# Qwiic_Adaptive_Switch_Output.net
KiCad netlist of a schematic drawn in EAGLE
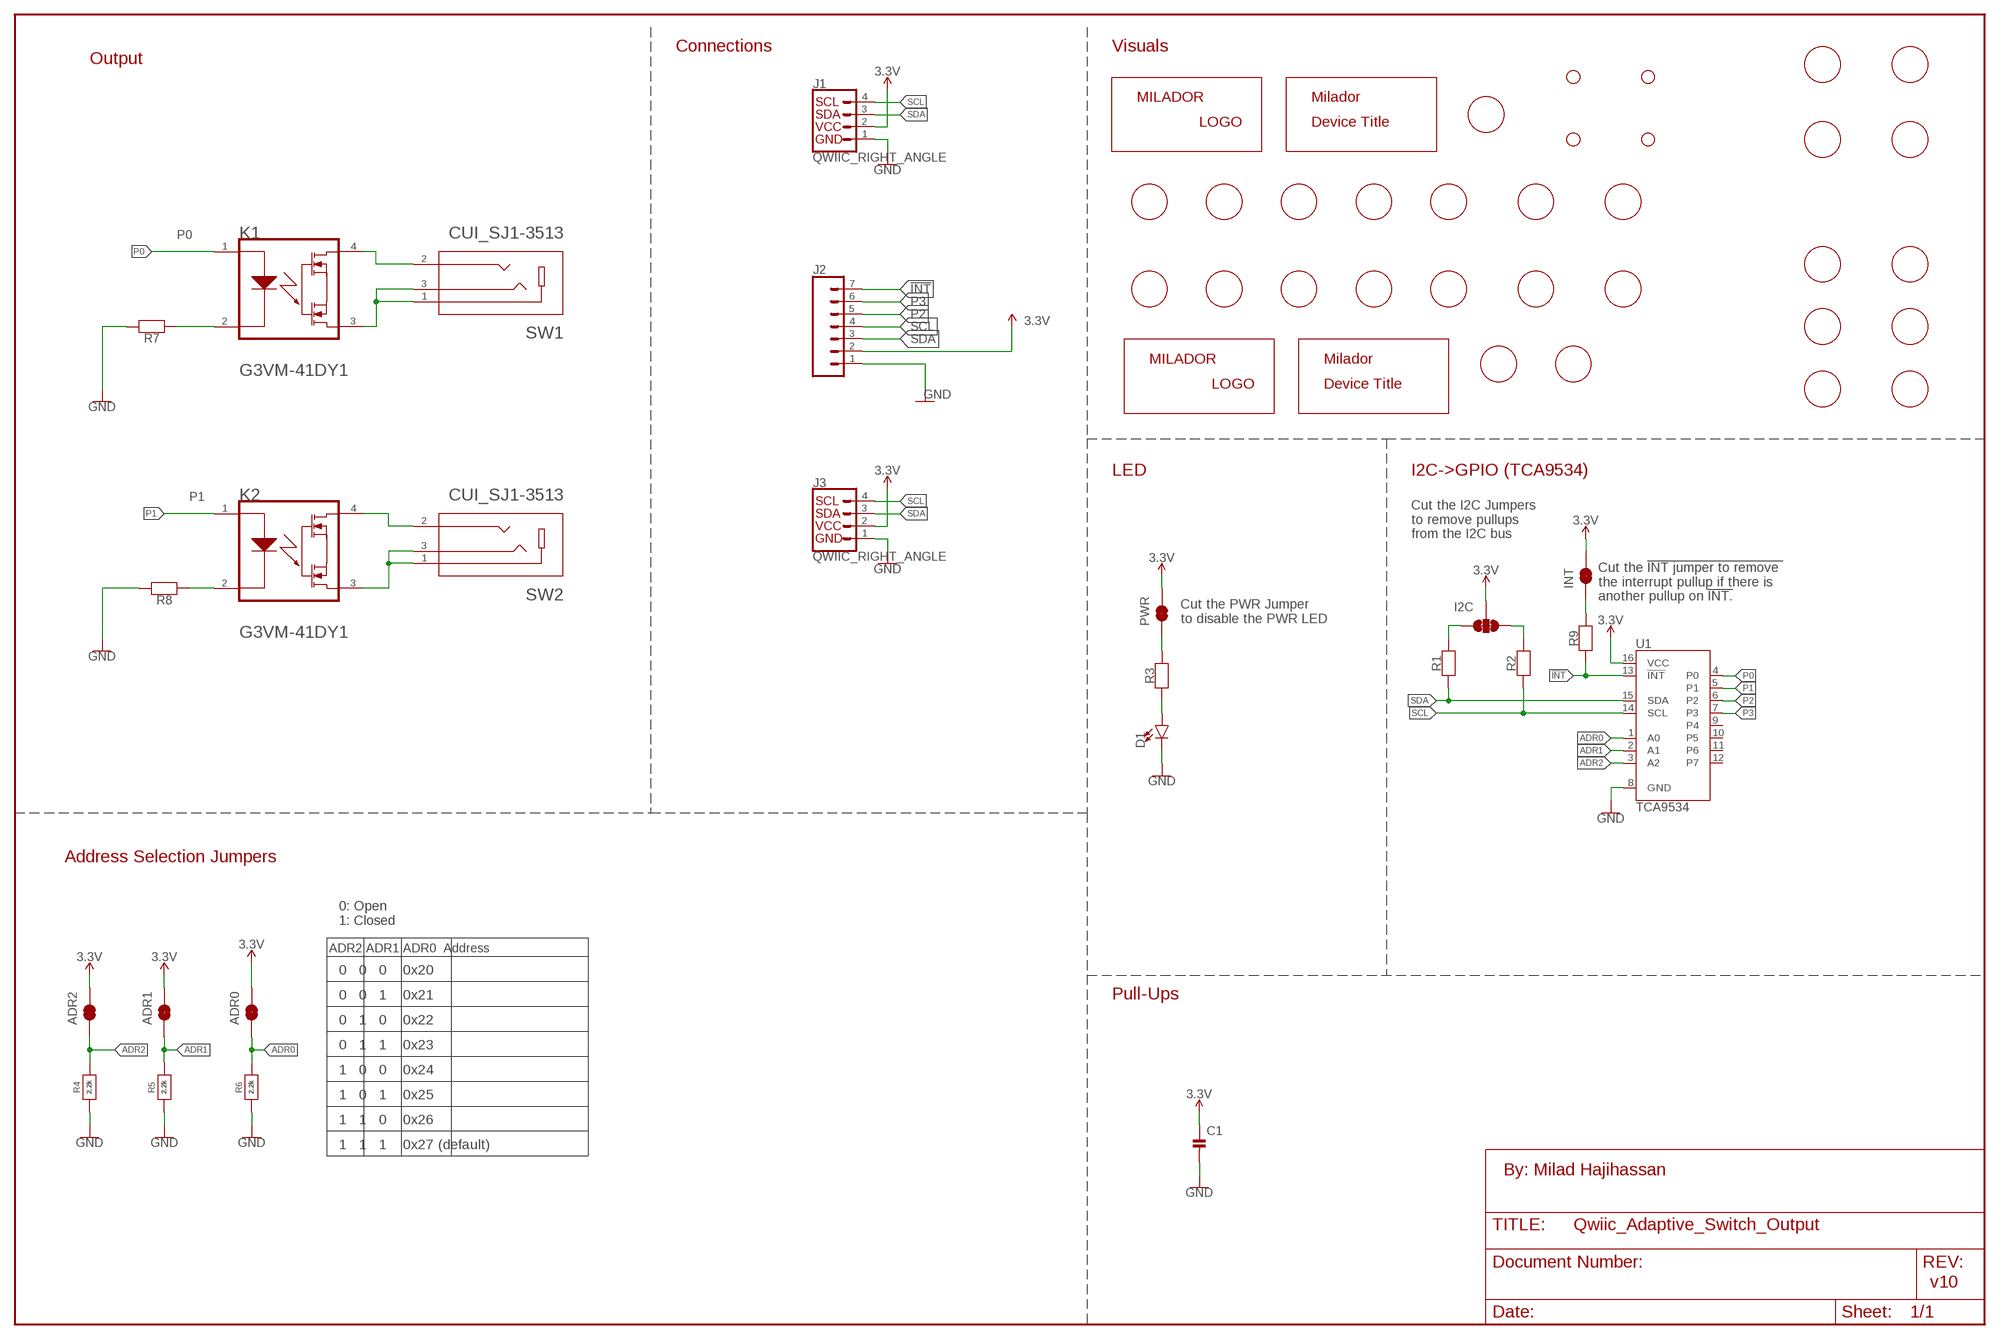
[diagram p0: schematic, sheet 1]

(export (version "E")
  (design (tool "Eeschema 10.0.6"))
  (components
    (comp (ref "ADR0")
      (value "JUMPERS-SMT_2_NC_TRACE_SILK")
      (footprint "eagle-import:JUMPERS_SMT-JUMPER_2_NC_TRACE_SILK")
      (libsource (lib "eagle-import") (part "JUMPERS-SMT_2_NC_TRACE_SILK"))
    )
    (comp (ref "ADR1")
      (value "JUMPERS-SMT_2_NC_TRACE_SILK")
      (footprint "eagle-import:JUMPERS_SMT-JUMPER_2_NC_TRACE_SILK")
      (libsource (lib "eagle-import") (part "JUMPERS-SMT_2_NC_TRACE_SILK"))
    )
    (comp (ref "ADR2")
      (value "JUMPERS-SMT_2_NC_TRACE_SILK")
      (footprint "eagle-import:JUMPERS_SMT-JUMPER_2_NC_TRACE_SILK")
      (libsource (lib "eagle-import") (part "JUMPERS-SMT_2_NC_TRACE_SILK"))
    )
    (comp (ref "C1")
      (value "0.1uF")
      (footprint "eagle-import:0805-MP")
      (libsource (lib "eagle-import") (part "CAP_CERAMIC-0805-MP"))
    )
    (comp (ref "D1")
      (value "RED")
      (footprint "eagle-import:CHIPLED_0805_NOOUTLINE")
      (libsource (lib "eagle-import") (part "LED0805_NOOUTLINE"))
    )
    (comp (ref "H1")
      (value "STAND-OFF-3.3")
      (footprint "eagle-import:STAND-OFF-3.3")
      (libsource (lib "eagle-import") (part "STAND-OFF-3.3"))
    )
    (comp (ref "H2")
      (value "STAND-OFF-3.3")
      (footprint "eagle-import:STAND-OFF-3.3")
      (libsource (lib "eagle-import") (part "STAND-OFF-3.3"))
    )
    (comp (ref "H3")
      (value "STAND-OFF-3.3")
      (footprint "eagle-import:STAND-OFF-3.3")
      (libsource (lib "eagle-import") (part "STAND-OFF-3.3"))
    )
    (comp (ref "H4")
      (value "STAND-OFF-3.3")
      (footprint "eagle-import:STAND-OFF-3.3")
      (libsource (lib "eagle-import") (part "STAND-OFF-3.3"))
    )
    (comp (ref "I2C")
      (value "JUMPERS_JUMPER-SMT_3_2-NC_TRACE_SILK")
      (footprint "eagle-import:JUMPERS_SMT-JUMPER_3_2-NC_TRACE_SILK")
      (libsource (lib "eagle-import") (part "JUMPERS_JUMPER-SMT_3_2-NC_TRACE_SILK"))
    )
    (comp (ref "INT")
      (value "JUMPERS-SMT_2_NC_TRACE_SILK")
      (footprint "eagle-import:JUMPERS_SMT-JUMPER_2_NC_TRACE_SILK")
      (libsource (lib "eagle-import") (part "JUMPERS-SMT_2_NC_TRACE_SILK"))
    )
    (comp (ref "J1")
      (value "QWIIC_RIGHT_ANGLE")
      (footprint "eagle-import:CONNECTORS_JST04_1MM_RA")
      (fields (field (name "PROD_ID") "CONN-13694"))
      (libsource (lib "eagle-import") (part "QWIIC_CONNECTORSJS-1MM"))
    )
    (comp (ref "J2")
      (value "CONNECTORS_CONN_071X07_NO_SILK")
      (footprint "eagle-import:CONNECTORS_1X07_NO_SILK")
      (libsource (lib "eagle-import") (part "CONNECTORS_CONN_071X07_NO_SILK"))
    )
    (comp (ref "J3")
      (value "QWIIC_RIGHT_ANGLE")
      (footprint "eagle-import:CONNECTORS_JST04_1MM_RA")
      (fields (field (name "PROD_ID") "CONN-13694"))
      (libsource (lib "eagle-import") (part "QWIIC_CONNECTORSJS-1MM"))
    )
    (comp (ref "K1")
      (value "G3VM-41DY1")
      (footprint "eagle-import:G3VM-41DY1")
      (libsource (lib "eagle-import") (part "G3VM-41DY1"))
    )
    (comp (ref "K2")
      (value "G3VM-41DY1")
      (footprint "eagle-import:G3VM-41DY1")
      (libsource (lib "eagle-import") (part "G3VM-41DY1"))
    )
    (comp (ref "LABEL_!INT_BOTTOM")
      (value "MILADOR-LABEL-!INT")
      (footprint "eagle-import:LABEL-!INT")
      (libsource (lib "eagle-import") (part "MILADOR-LABEL-!INT"))
    )
    (comp (ref "LABEL_!INT_TOP")
      (value "MILADOR-LABEL-!INT")
      (footprint "eagle-import:LABEL-!INT")
      (libsource (lib "eagle-import") (part "MILADOR-LABEL-!INT"))
    )
    (comp (ref "LABEL_3V_BOTTOM")
      (value "MILADOR-LABEL-3V")
      (footprint "eagle-import:LABEL-3V")
      (libsource (lib "eagle-import") (part "MILADOR-LABEL-3V"))
    )
    (comp (ref "LABEL_3V_TOP")
      (value "MILADOR-LABEL-3V")
      (footprint "eagle-import:LABEL-3V")
      (libsource (lib "eagle-import") (part "MILADOR-LABEL-3V"))
    )
    (comp (ref "LABEL_ADR0")
      (value "MILADOR-LABEL-ADR0")
      (footprint "eagle-import:LABEL-ADR0")
      (libsource (lib "eagle-import") (part "MILADOR-LABEL-ADR0"))
    )
    (comp (ref "LABEL_ADR1")
      (value "MILADOR-LABEL-ADR1")
      (footprint "eagle-import:LABEL-ADR1")
      (libsource (lib "eagle-import") (part "MILADOR-LABEL-ADR1"))
    )
    (comp (ref "LABEL_ADR2")
      (value "MILADOR-LABEL-ADR2")
      (footprint "eagle-import:LABEL-ADR2")
      (libsource (lib "eagle-import") (part "MILADOR-LABEL-ADR2"))
    )
    (comp (ref "LABEL_GND_BOTTOM")
      (value "MILADOR-LABEL-GND")
      (footprint "eagle-import:LABEL-GND")
      (libsource (lib "eagle-import") (part "MILADOR-LABEL-GND"))
    )
    (comp (ref "LABEL_GND_TOP")
      (value "MILADOR-LABEL-GND")
      (footprint "eagle-import:LABEL-GND")
      (libsource (lib "eagle-import") (part "MILADOR-LABEL-GND"))
    )
    (comp (ref "LABEL_I2C")
      (value "MILADOR-LABEL-I2C")
      (footprint "eagle-import:LABEL-I2C")
      (libsource (lib "eagle-import") (part "MILADOR-LABEL-I2C"))
    )
    (comp (ref "LABEL_I2C_ADDRESS")
      (value "MILADOR-LABEL-ADDRESS-0X27")
      (footprint "eagle-import:LABEL-ADDRESS-27")
      (libsource (lib "eagle-import") (part "MILADOR-LABEL-ADDRESS-0X27"))
    )
    (comp (ref "LABEL_INT")
      (value "MILADOR-LABEL-INT")
      (footprint "eagle-import:LABEL-INT")
      (libsource (lib "eagle-import") (part "MILADOR-LABEL-INT"))
    )
    (comp (ref "LABEL_MILADOR_BOTTOM")
      (value "MILADOR-LOGO-")
      (footprint "eagle-import:MILADOR_LOGO1")
      (libsource (lib "eagle-import") (part "MILADOR-LOGO-"))
    )
    (comp (ref "LABEL_MILADOR_TOP")
      (value "MILADOR-LOGO-")
      (footprint "eagle-import:MILADOR_LOGO1")
      (libsource (lib "eagle-import") (part "MILADOR-LOGO-"))
    )
    (comp (ref "LABEL_OUTPUT_BOTTOM")
      (value "MILADOR-SWITCH-NAME-SW-OUTPUT")
      (footprint "eagle-import:SWITCH-OUTPUT")
      (libsource (lib "eagle-import") (part "MILADOR-SWITCH-NAME-SW-OUTPUT"))
    )
    (comp (ref "LABEL_OUTPUT_TOP")
      (value "MILADOR-SWITCH-NAME-SW-OUTPUT")
      (footprint "eagle-import:SWITCH-OUTPUT")
      (libsource (lib "eagle-import") (part "MILADOR-SWITCH-NAME-SW-OUTPUT"))
    )
    (comp (ref "LABEL_P0_BOTTOM")
      (value "MILADOR-LABEL-P0")
      (footprint "eagle-import:LABEL-P0")
      (libsource (lib "eagle-import") (part "MILADOR-LABEL-P0"))
    )
    (comp (ref "LABEL_P1_BOTTOM")
      (value "MILADOR-LABEL-P1")
      (footprint "eagle-import:LABEL-P1")
      (libsource (lib "eagle-import") (part "MILADOR-LABEL-P1"))
    )
    (comp (ref "LABEL_P2_BOTTOM")
      (value "MILADOR-LABEL-P2")
      (footprint "eagle-import:LABEL-P2")
      (libsource (lib "eagle-import") (part "MILADOR-LABEL-P2"))
    )
    (comp (ref "LABEL_P2_TOP")
      (value "MILADOR-LABEL-P2")
      (footprint "eagle-import:LABEL-P2")
      (libsource (lib "eagle-import") (part "MILADOR-LABEL-P2"))
    )
    (comp (ref "LABEL_P3_BOTTOM")
      (value "MILADOR-LABEL-P3")
      (footprint "eagle-import:LABEL-P3")
      (libsource (lib "eagle-import") (part "MILADOR-LABEL-P3"))
    )
    (comp (ref "LABEL_P3_TOP")
      (value "MILADOR-LABEL-P3")
      (footprint "eagle-import:LABEL-P3")
      (libsource (lib "eagle-import") (part "MILADOR-LABEL-P3"))
    )
    (comp (ref "LABEL_PWR")
      (value "MILADOR-LABEL-PWR")
      (footprint "eagle-import:LABEL-PWR")
      (libsource (lib "eagle-import") (part "MILADOR-LABEL-PWR"))
    )
    (comp (ref "LABEL_SW1")
      (value "MILADOR-SWITCH-NAME-SW1")
      (footprint "eagle-import:SWITCH-SW1")
      (libsource (lib "eagle-import") (part "MILADOR-SWITCH-NAME-SW1"))
    )
    (comp (ref "LABEL_SW2")
      (value "MILADOR-SWITCH-NAME-SW2")
      (footprint "eagle-import:SWITCH-SW2")
      (libsource (lib "eagle-import") (part "MILADOR-SWITCH-NAME-SW2"))
    )
    (comp (ref "LABEL_TITLE_BOTTOM")
      (value "MILADOR-DEVICE-QWIIC-SWITCH")
      (footprint "eagle-import:MILADOR_QWIIC_SWITCH")
      (libsource (lib "eagle-import") (part "MILADOR-DEVICE-QWIIC-SWITCH"))
    )
    (comp (ref "LABEL_TITLE_TOP")
      (value "MILADOR-DEVICE-QWIIC-SWITCH-SM")
      (footprint "eagle-import:MILADOR_QWIIC_SWITCH_SM")
      (libsource (lib "eagle-import") (part "MILADOR-DEVICE-QWIIC-SWITCH-SM"))
    )
    (comp (ref "LABE_SCL_BOTTOM")
      (value "MILADOR-LABEL-SCL")
      (footprint "eagle-import:LABEL-SCL")
      (libsource (lib "eagle-import") (part "MILADOR-LABEL-SCL"))
    )
    (comp (ref "LABE_SCL_TOP")
      (value "MILADOR-LABEL-SCL")
      (footprint "eagle-import:LABEL-SCL")
      (libsource (lib "eagle-import") (part "MILADOR-LABEL-SCL"))
    )
    (comp (ref "LABE_SDA_BOTTOM")
      (value "MILADOR-LABEL-SDA")
      (footprint "eagle-import:LABEL-SDA")
      (libsource (lib "eagle-import") (part "MILADOR-LABEL-SDA"))
    )
    (comp (ref "LABE_SDA_TOP")
      (value "MILADOR-LABEL-SDA")
      (footprint "eagle-import:LABEL-SDA")
      (libsource (lib "eagle-import") (part "MILADOR-LABEL-SDA"))
    )
    (comp (ref "PWR")
      (value "JUMPERS-SMT_2_NC_TRACE_SILK")
      (footprint "eagle-import:JUMPERS_SMT-JUMPER_2_NC_TRACE_SILK")
      (libsource (lib "eagle-import") (part "JUMPERS-SMT_2_NC_TRACE_SILK"))
    )
    (comp (ref "R1")
      (value "2.2k")
      (footprint "eagle-import:0805-MP")
      (libsource (lib "eagle-import") (part "RESISTOR-0805-MP"))
    )
    (comp (ref "R2")
      (value "2.2k")
      (footprint "eagle-import:0805-MP")
      (libsource (lib "eagle-import") (part "RESISTOR-0805-MP"))
    )
    (comp (ref "R3")
      (value "1k")
      (footprint "eagle-import:0805-MP")
      (libsource (lib "eagle-import") (part "RESISTOR-0805-MP"))
    )
    (comp (ref "R4")
      (value "2.2k")
      (footprint "eagle-import:0805-MP")
      (libsource (lib "eagle-import") (part "RESISTOR-0805-MP"))
    )
    (comp (ref "R5")
      (value "2.2k")
      (footprint "eagle-import:0805-MP")
      (libsource (lib "eagle-import") (part "RESISTOR-0805-MP"))
    )
    (comp (ref "R6")
      (value "2.2k")
      (footprint "eagle-import:0805-MP")
      (libsource (lib "eagle-import") (part "RESISTOR-0805-MP"))
    )
    (comp (ref "R7")
      (value "220")
      (footprint "eagle-import:0805-MP")
      (libsource (lib "eagle-import") (part "RESISTOR-0805-MP"))
    )
    (comp (ref "R8")
      (value "220")
      (footprint "eagle-import:0805-MP")
      (libsource (lib "eagle-import") (part "RESISTOR-0805-MP"))
    )
    (comp (ref "R9")
      (value "10k")
      (footprint "eagle-import:0805-MP")
      (libsource (lib "eagle-import") (part "RESISTOR-0805-MP"))
    )
    (comp (ref "SW1")
      (value "CUI_SJ1-3513")
      (footprint "eagle-import:CUI_SJ1-3513")
      (libsource (lib "eagle-import") (part "CUI_SJ1-3513"))
    )
    (comp (ref "SW2")
      (value "CUI_SJ1-3513")
      (footprint "eagle-import:CUI_SJ1-3513")
      (libsource (lib "eagle-import") (part "CUI_SJ1-3513"))
    )
    (comp (ref "U1")
      (value "TCA9534")
      (footprint "eagle-import:16SOIC")
      (libsource (lib "eagle-import") (part "TCA9534DWR"))
    )
  )
  (nets
    (net (code "1") (name "/~{INT}") (class "Default")
      (node (ref "J2") (pin "7") (pinfunction "7_7") (pintype "passive"))
      (node (ref "R9") (pin "1") (pinfunction "1_1") (pintype "passive"))
      (node (ref "U1") (pin "13") (pinfunction "~{INT}_13") (pintype "bidirectional"))
    )
    (net (code "2") (name "3.3V") (class "Default")
      (node (ref "ADR0") (pin "2") (pinfunction "2_2") (pintype "passive"))
      (node (ref "ADR1") (pin "2") (pinfunction "2_2") (pintype "passive"))
      (node (ref "ADR2") (pin "2") (pinfunction "2_2") (pintype "passive"))
      (node (ref "C1") (pin "1") (pinfunction "1_1") (pintype "passive"))
      (node (ref "I2C") (pin "2") (pinfunction "2_2") (pintype "passive"))
      (node (ref "INT") (pin "2") (pinfunction "2_2") (pintype "passive"))
      (node (ref "J1") (pin "2") (pinfunction "2_2") (pintype "power_in"))
      (node (ref "J2") (pin "2") (pinfunction "2_2") (pintype "passive"))
      (node (ref "J3") (pin "2") (pinfunction "2_2") (pintype "power_in"))
      (node (ref "PWR") (pin "2") (pinfunction "2_2") (pintype "passive"))
      (node (ref "U1") (pin "16") (pinfunction "VCC_16") (pintype "bidirectional"))
    )
    (net (code "3") (name "ADR0") (class "Default")
      (node (ref "ADR0") (pin "1") (pinfunction "1_1") (pintype "passive"))
      (node (ref "R6") (pin "2") (pinfunction "2_2") (pintype "passive"))
      (node (ref "U1") (pin "1") (pinfunction "A0_1") (pintype "bidirectional"))
    )
    (net (code "4") (name "ADR1") (class "Default")
      (node (ref "ADR1") (pin "1") (pinfunction "1_1") (pintype "passive"))
      (node (ref "R5") (pin "2") (pinfunction "2_2") (pintype "passive"))
      (node (ref "U1") (pin "2") (pinfunction "A1_2") (pintype "bidirectional"))
    )
    (net (code "5") (name "ADR2") (class "Default")
      (node (ref "ADR2") (pin "1") (pinfunction "1_1") (pintype "passive"))
      (node (ref "R4") (pin "2") (pinfunction "2_2") (pintype "passive"))
      (node (ref "U1") (pin "3") (pinfunction "A2_3") (pintype "bidirectional"))
    )
    (net (code "6") (name "GND") (class "Default")
      (node (ref "C1") (pin "2") (pinfunction "2_2") (pintype "passive"))
      (node (ref "D1") (pin "C") (pinfunction "C_C") (pintype "passive"))
      (node (ref "J1") (pin "1") (pinfunction "1_1") (pintype "power_in"))
      (node (ref "J2") (pin "1") (pinfunction "1_1") (pintype "passive"))
      (node (ref "J3") (pin "1") (pinfunction "1_1") (pintype "power_in"))
      (node (ref "R4") (pin "1") (pinfunction "1_1") (pintype "passive"))
      (node (ref "R5") (pin "1") (pinfunction "1_1") (pintype "passive"))
      (node (ref "R6") (pin "1") (pinfunction "1_1") (pintype "passive"))
      (node (ref "R7") (pin "2") (pinfunction "2_2") (pintype "passive"))
      (node (ref "R8") (pin "2") (pinfunction "2_2") (pintype "passive"))
      (node (ref "U1") (pin "8") (pinfunction "GND_8") (pintype "bidirectional"))
    )
    (net (code "7") (name "Net-(D1-PadA)") (class "Default")
      (node (ref "D1") (pin "A") (pinfunction "A_A") (pintype "passive"))
      (node (ref "R3") (pin "1") (pinfunction "1_1") (pintype "passive"))
    )
    (net (code "8") (name "Net-(I2C-Pad1)") (class "Default")
      (node (ref "I2C") (pin "1") (pinfunction "1_1") (pintype "passive"))
      (node (ref "R1") (pin "2") (pinfunction "2_2") (pintype "passive"))
    )
    (net (code "9") (name "Net-(I2C-Pad3)") (class "Default")
      (node (ref "I2C") (pin "3") (pinfunction "3_3") (pintype "passive"))
      (node (ref "R2") (pin "2") (pinfunction "2_2") (pintype "passive"))
    )
    (net (code "10") (name "Net-(INT-Pad1)") (class "Default")
      (node (ref "INT") (pin "1") (pinfunction "1_1") (pintype "passive"))
      (node (ref "R9") (pin "2") (pinfunction "2_2") (pintype "passive"))
    )
    (net (code "11") (name "Net-(K1-Pad2)") (class "Default")
      (node (ref "K1") (pin "2") (pinfunction "2_2") (pintype "passive"))
      (node (ref "R7") (pin "1") (pinfunction "1_1") (pintype "passive"))
    )
    (net (code "12") (name "Net-(K1-Pad3)") (class "Default")
      (node (ref "K1") (pin "3") (pinfunction "3_3") (pintype "passive"))
      (node (ref "SW1") (pin "1") (pinfunction "1_1") (pintype "passive"))
      (node (ref "SW1") (pin "3") (pinfunction "3_3") (pintype "passive"))
    )
    (net (code "13") (name "Net-(K1-Pad4)") (class "Default")
      (node (ref "K1") (pin "4") (pinfunction "4_4") (pintype "passive"))
      (node (ref "SW1") (pin "2") (pinfunction "2_2") (pintype "passive"))
    )
    (net (code "14") (name "Net-(K2-Pad2)") (class "Default")
      (node (ref "K2") (pin "2") (pinfunction "2_2") (pintype "passive"))
      (node (ref "R8") (pin "1") (pinfunction "1_1") (pintype "passive"))
    )
    (net (code "15") (name "Net-(K2-Pad3)") (class "Default")
      (node (ref "K2") (pin "3") (pinfunction "3_3") (pintype "passive"))
      (node (ref "SW2") (pin "1") (pinfunction "1_1") (pintype "passive"))
      (node (ref "SW2") (pin "3") (pinfunction "3_3") (pintype "passive"))
    )
    (net (code "16") (name "Net-(K2-Pad4)") (class "Default")
      (node (ref "K2") (pin "4") (pinfunction "4_4") (pintype "passive"))
      (node (ref "SW2") (pin "2") (pinfunction "2_2") (pintype "passive"))
    )
    (net (code "17") (name "Net-(PWR-Pad1)") (class "Default")
      (node (ref "PWR") (pin "1") (pinfunction "1_1") (pintype "passive"))
      (node (ref "R3") (pin "2") (pinfunction "2_2") (pintype "passive"))
    )
    (net (code "18") (name "P0") (class "Default")
      (node (ref "K1") (pin "1") (pinfunction "1_1") (pintype "passive"))
      (node (ref "U1") (pin "4") (pinfunction "P0_4") (pintype "bidirectional"))
    )
    (net (code "19") (name "P1") (class "Default")
      (node (ref "K2") (pin "1") (pinfunction "1_1") (pintype "passive"))
      (node (ref "U1") (pin "5") (pinfunction "P1_5") (pintype "bidirectional"))
    )
    (net (code "20") (name "P2") (class "Default")
      (node (ref "J2") (pin "5") (pinfunction "5_5") (pintype "passive"))
      (node (ref "U1") (pin "6") (pinfunction "P2_6") (pintype "bidirectional"))
    )
    (net (code "21") (name "P3") (class "Default")
      (node (ref "J2") (pin "6") (pinfunction "6_6") (pintype "passive"))
      (node (ref "U1") (pin "7") (pinfunction "P3_7") (pintype "bidirectional"))
    )
    (net (code "22") (name "SCL") (class "Default")
      (node (ref "J1") (pin "4") (pinfunction "4_4") (pintype "passive"))
      (node (ref "J2") (pin "4") (pinfunction "4_4") (pintype "passive"))
      (node (ref "J3") (pin "4") (pinfunction "4_4") (pintype "passive"))
      (node (ref "R2") (pin "1") (pinfunction "1_1") (pintype "passive"))
      (node (ref "U1") (pin "14") (pinfunction "SCL_14") (pintype "bidirectional"))
    )
    (net (code "23") (name "SDA") (class "Default")
      (node (ref "J1") (pin "3") (pinfunction "3_3") (pintype "passive"))
      (node (ref "J2") (pin "3") (pinfunction "3_3") (pintype "passive"))
      (node (ref "J3") (pin "3") (pinfunction "3_3") (pintype "passive"))
      (node (ref "R1") (pin "1") (pinfunction "1_1") (pintype "passive"))
      (node (ref "U1") (pin "15") (pinfunction "SDA_15") (pintype "bidirectional"))
    )
    (net (code "24") (name "unconnected-(U1-P4-Pad9)") (class "Default")
      (node (ref "U1") (pin "9") (pinfunction "P4_9") (pintype "bidirectional"))
    )
    (net (code "25") (name "unconnected-(U1-P5-Pad10)") (class "Default")
      (node (ref "U1") (pin "10") (pinfunction "P5_10") (pintype "bidirectional"))
    )
    (net (code "26") (name "unconnected-(U1-P6-Pad11)") (class "Default")
      (node (ref "U1") (pin "11") (pinfunction "P6_11") (pintype "bidirectional"))
    )
    (net (code "27") (name "unconnected-(U1-P7-Pad12)") (class "Default")
      (node (ref "U1") (pin "12") (pinfunction "P7_12") (pintype "bidirectional"))
    )
  )
)
